# board.net
KiCad netlist of a schematic drawn in EAGLE
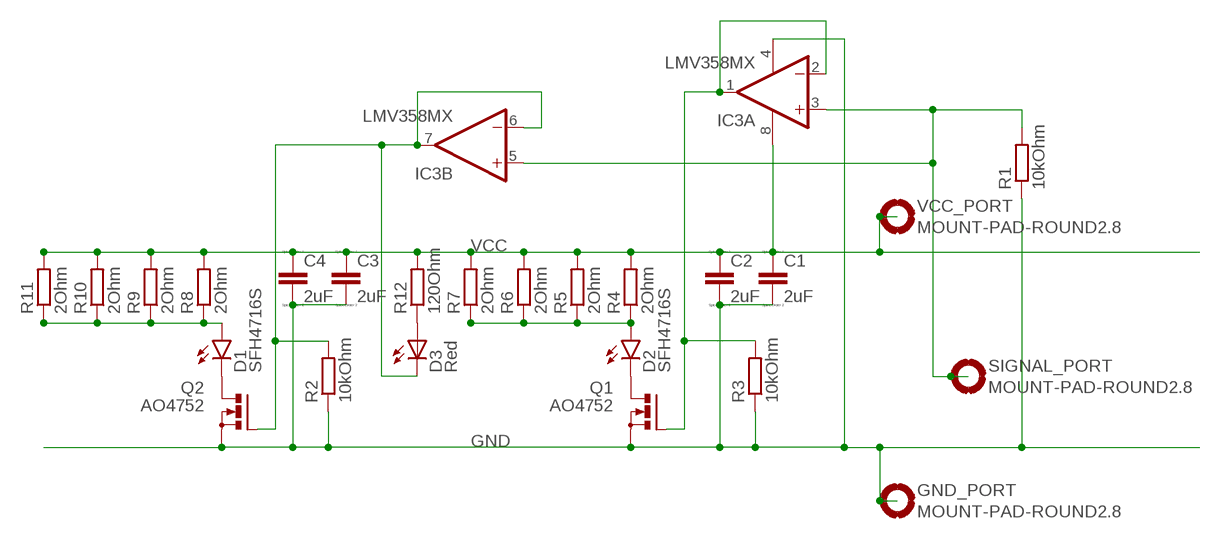
[diagram p0: schematic, sheet 1]

(export (version "E")
  (design (tool "Eeschema 10.0.6"))
  (components
    (comp (ref "C1")
      (value "2uF")
      (footprint "eagle-import:C0603")
      (libsource (lib "eagle-import") (part "CC0603"))
    )
    (comp (ref "C2")
      (value "2uF")
      (footprint "eagle-import:C0603")
      (libsource (lib "eagle-import") (part "CC0603"))
    )
    (comp (ref "C3")
      (value "2uF")
      (footprint "eagle-import:C0603")
      (libsource (lib "eagle-import") (part "CC0603"))
    )
    (comp (ref "C4")
      (value "2uF")
      (footprint "eagle-import:C0603")
      (libsource (lib "eagle-import") (part "CC0603"))
    )
    (comp (ref "D1")
      (value "SFH4716S")
      (footprint "eagle-import:SFH4641")
      (libsource (lib "eagle-import") (part "SFH4641LARGE"))
    )
    (comp (ref "D2")
      (value "SFH4716S")
      (footprint "eagle-import:SFH4641")
      (libsource (lib "eagle-import") (part "SFH4641LARGE"))
    )
    (comp (ref "D3")
      (value "Red")
      (footprint "eagle-import:LED5MM")
      (libsource (lib "eagle-import") (part "LED5MM"))
    )
    (comp (ref "GND_PORT")
      (value "MOUNT-PAD-ROUND2.8")
      (footprint "eagle-import:2,8-PAD")
      (libsource (lib "eagle-import") (part "MOUNT-PAD-ROUND2.8"))
    )
    (comp (ref "IC3")
      (value "LMV358MX")
      (footprint "eagle-import:SO08")
      (libsource (lib "eagle-import") (part "LMV358?MX"))
    )
    (comp (ref "Q1")
      (value "AO4752")
      (footprint "eagle-import:SO-08")
      (libsource (lib "eagle-import") (part "N-MOSFET-SO8S"))
    )
    (comp (ref "Q2")
      (value "AO4752")
      (footprint "eagle-import:SO-08")
      (libsource (lib "eagle-import") (part "N-MOSFET-SO8S"))
    )
    (comp (ref "R1")
      (value "10kOhm")
      (footprint "eagle-import:R0603")
      (libsource (lib "eagle-import") (part "resistor_R-EU_R0603"))
    )
    (comp (ref "R2")
      (value "10kOhm")
      (footprint "eagle-import:R0603")
      (libsource (lib "eagle-import") (part "resistor_R-EU_R0603"))
    )
    (comp (ref "R3")
      (value "10kOhm")
      (footprint "eagle-import:R0603")
      (libsource (lib "eagle-import") (part "resistor_R-EU_R0603"))
    )
    (comp (ref "R4")
      (value "2Ohm")
      (footprint "eagle-import:R2512")
      (libsource (lib "eagle-import") (part "R-EU_R2512"))
    )
    (comp (ref "R5")
      (value "2Ohm")
      (footprint "eagle-import:R2512")
      (libsource (lib "eagle-import") (part "R-EU_R2512"))
    )
    (comp (ref "R6")
      (value "2Ohm")
      (footprint "eagle-import:R2512")
      (libsource (lib "eagle-import") (part "R-EU_R2512"))
    )
    (comp (ref "R7")
      (value "2Ohm")
      (footprint "eagle-import:R2512")
      (libsource (lib "eagle-import") (part "R-EU_R2512"))
    )
    (comp (ref "R8")
      (value "2Ohm")
      (footprint "eagle-import:R2512")
      (libsource (lib "eagle-import") (part "R-EU_R2512"))
    )
    (comp (ref "R9")
      (value "2Ohm")
      (footprint "eagle-import:R2512")
      (libsource (lib "eagle-import") (part "R-EU_R2512"))
    )
    (comp (ref "R10")
      (value "2Ohm")
      (footprint "eagle-import:R2512")
      (libsource (lib "eagle-import") (part "R-EU_R2512"))
    )
    (comp (ref "R11")
      (value "2Ohm")
      (footprint "eagle-import:R2512")
      (libsource (lib "eagle-import") (part "R-EU_R2512"))
    )
    (comp (ref "R12")
      (value "120Ohm")
      (footprint "eagle-import:R0603")
      (libsource (lib "eagle-import") (part "resistor_R-EU_R0603"))
    )
    (comp (ref "SIGNAL_PORT")
      (value "MOUNT-PAD-ROUND2.8")
      (footprint "eagle-import:2,8-PAD")
      (libsource (lib "eagle-import") (part "MOUNT-PAD-ROUND2.8"))
    )
    (comp (ref "VCC_PORT")
      (value "MOUNT-PAD-ROUND2.8")
      (footprint "eagle-import:2,8-PAD")
      (libsource (lib "eagle-import") (part "MOUNT-PAD-ROUND2.8"))
    )
  )
  (nets
    (net (code "1") (name "/GND") (class "Default")
      (node (ref "C1") (pin "2") (pinfunction "2_2") (pintype "passive"))
      (node (ref "C2") (pin "2") (pinfunction "2_2") (pintype "passive"))
      (node (ref "C3") (pin "2") (pinfunction "2_2") (pintype "passive"))
      (node (ref "C4") (pin "2") (pinfunction "2_2") (pintype "passive"))
      (node (ref "GND_PORT") (pin "B2,8") (pinfunction "MOUNT_B2,8") (pintype "passive"))
      (node (ref "IC3") (pin "4") (pinfunction "V-_4") (pintype "power_in"))
      (node (ref "Q1") (pin "1") (pinfunction "S_1") (pintype "passive"))
      (node (ref "Q1") (pin "2") (pinfunction "S_2") (pintype "passive"))
      (node (ref "Q1") (pin "3") (pinfunction "S_3") (pintype "passive"))
      (node (ref "Q2") (pin "1") (pinfunction "S_1") (pintype "passive"))
      (node (ref "Q2") (pin "2") (pinfunction "S_2") (pintype "passive"))
      (node (ref "Q2") (pin "3") (pinfunction "S_3") (pintype "passive"))
      (node (ref "R1") (pin "1") (pinfunction "1_1") (pintype "passive"))
      (node (ref "R2") (pin "1") (pinfunction "1_1") (pintype "passive"))
      (node (ref "R3") (pin "1") (pinfunction "1_1") (pintype "passive"))
    )
    (net (code "2") (name "/VCC") (class "Default")
      (node (ref "C1") (pin "1") (pinfunction "1_1") (pintype "passive"))
      (node (ref "C2") (pin "1") (pinfunction "1_1") (pintype "passive"))
      (node (ref "C3") (pin "1") (pinfunction "1_1") (pintype "passive"))
      (node (ref "C4") (pin "1") (pinfunction "1_1") (pintype "passive"))
      (node (ref "IC3") (pin "8") (pinfunction "V+_8") (pintype "power_in"))
      (node (ref "R10") (pin "2") (pinfunction "2_2") (pintype "passive"))
      (node (ref "R11") (pin "2") (pinfunction "2_2") (pintype "passive"))
      (node (ref "R12") (pin "2") (pinfunction "2_2") (pintype "passive"))
      (node (ref "R4") (pin "2") (pinfunction "2_2") (pintype "passive"))
      (node (ref "R5") (pin "2") (pinfunction "2_2") (pintype "passive"))
      (node (ref "R6") (pin "2") (pinfunction "2_2") (pintype "passive"))
      (node (ref "R7") (pin "2") (pinfunction "2_2") (pintype "passive"))
      (node (ref "R8") (pin "2") (pinfunction "2_2") (pintype "passive"))
      (node (ref "R9") (pin "2") (pinfunction "2_2") (pintype "passive"))
      (node (ref "VCC_PORT") (pin "B2,8") (pinfunction "MOUNT_B2,8") (pintype "passive"))
    )
    (net (code "3") (name "Net-(D1-PadA)") (class "Default")
      (node (ref "D1") (pin "A") (pinfunction "A_A") (pintype "passive"))
      (node (ref "R10") (pin "1") (pinfunction "1_1") (pintype "passive"))
      (node (ref "R11") (pin "1") (pinfunction "1_1") (pintype "passive"))
      (node (ref "R8") (pin "1") (pinfunction "1_1") (pintype "passive"))
      (node (ref "R9") (pin "1") (pinfunction "1_1") (pintype "passive"))
    )
    (net (code "4") (name "Net-(D1-PadC)") (class "Default")
      (node (ref "D1") (pin "C") (pinfunction "C_C") (pintype "passive"))
      (node (ref "Q2") (pin "5") (pinfunction "D_5") (pintype "passive"))
      (node (ref "Q2") (pin "6") (pinfunction "D_6") (pintype "passive"))
      (node (ref "Q2") (pin "7") (pinfunction "D_7") (pintype "passive"))
      (node (ref "Q2") (pin "8") (pinfunction "D_8") (pintype "passive"))
    )
    (net (code "5") (name "Net-(D2-PadA)") (class "Default")
      (node (ref "D2") (pin "A") (pinfunction "A_A") (pintype "passive"))
      (node (ref "R4") (pin "1") (pinfunction "1_1") (pintype "passive"))
      (node (ref "R5") (pin "1") (pinfunction "1_1") (pintype "passive"))
      (node (ref "R6") (pin "1") (pinfunction "1_1") (pintype "passive"))
      (node (ref "R7") (pin "1") (pinfunction "1_1") (pintype "passive"))
    )
    (net (code "6") (name "Net-(D2-PadC)") (class "Default")
      (node (ref "D2") (pin "C") (pinfunction "C_C") (pintype "passive"))
      (node (ref "Q1") (pin "5") (pinfunction "D_5") (pintype "passive"))
      (node (ref "Q1") (pin "6") (pinfunction "D_6") (pintype "passive"))
      (node (ref "Q1") (pin "7") (pinfunction "D_7") (pintype "passive"))
      (node (ref "Q1") (pin "8") (pinfunction "D_8") (pintype "passive"))
    )
    (net (code "7") (name "Net-(D3-C)") (class "Default")
      (node (ref "D3") (pin "K") (pinfunction "C_K") (pintype "passive"))
      (node (ref "IC3") (pin "6") (pinfunction "-IN_6") (pintype "input"))
      (node (ref "IC3") (pin "7") (pinfunction "OUT_7") (pintype "output"))
      (node (ref "Q2") (pin "4") (pinfunction "G_4") (pintype "passive"))
      (node (ref "R2") (pin "2") (pinfunction "2_2") (pintype "passive"))
    )
    (net (code "8") (name "Net-(D3-PadA)") (class "Default")
      (node (ref "D3") (pin "A") (pinfunction "A_A") (pintype "passive"))
      (node (ref "R12") (pin "1") (pinfunction "1_1") (pintype "passive"))
    )
    (net (code "9") (name "Net-(IC3A-+IN)") (class "Default")
      (node (ref "IC3") (pin "3") (pinfunction "+IN_3") (pintype "input"))
      (node (ref "IC3") (pin "5") (pinfunction "+IN_5") (pintype "input"))
      (node (ref "R1") (pin "2") (pinfunction "2_2") (pintype "passive"))
      (node (ref "SIGNAL_PORT") (pin "B2,8") (pinfunction "MOUNT_B2,8") (pintype "passive"))
    )
    (net (code "10") (name "Net-(IC3A--IN)") (class "Default")
      (node (ref "IC3") (pin "1") (pinfunction "OUT_1") (pintype "output"))
      (node (ref "IC3") (pin "2") (pinfunction "-IN_2") (pintype "input"))
      (node (ref "Q1") (pin "4") (pinfunction "G_4") (pintype "passive"))
      (node (ref "R3") (pin "2") (pinfunction "2_2") (pintype "passive"))
    )
  )
)
